# USB.net
KiCad netlist of a schematic drawn in Altium Designer
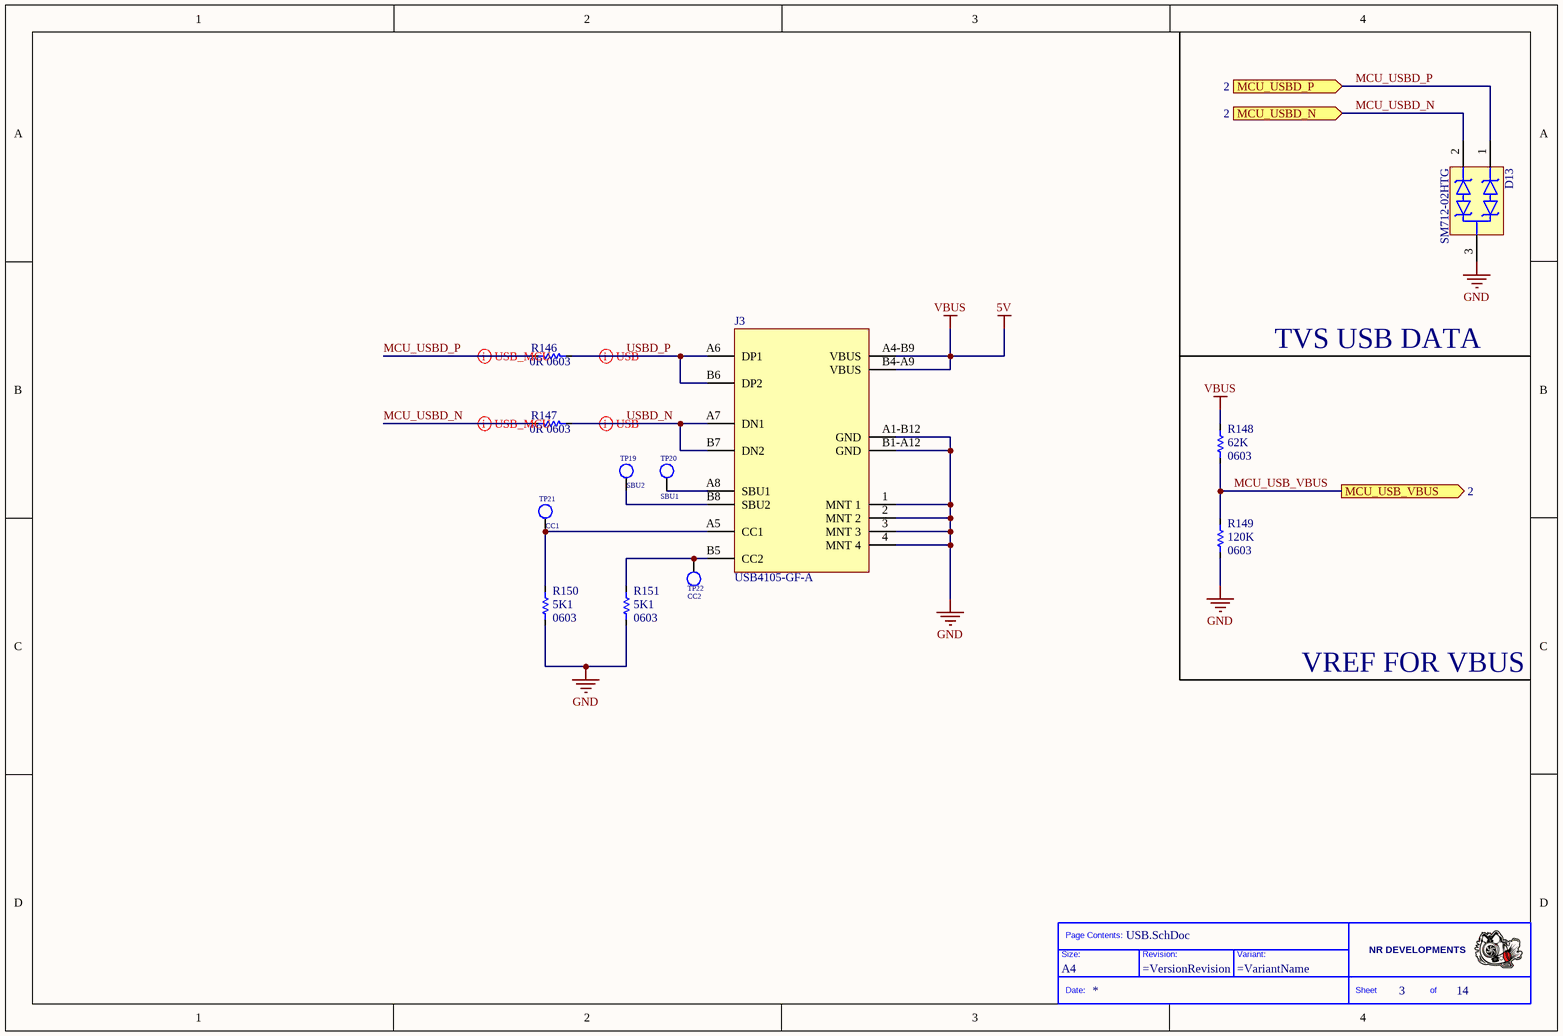
[diagram p0: USB.SchDoc]

(export (version "E")
  (design (tool "Eeschema 10.0.6"))
  (components
    (comp (ref "D13")
      (value "SM712-02HTG")
      (footprint "SOT95P240X120-3N")
      (description "ESD Diode bid -7 to 12v")
      (fields (field (name "MANUFACTURER") "Littelfuse"))
      (libsource (lib "My_LIB") (part "SM712-02HTG"))
    )
    (comp (ref "J3")
      (value "USB4105-GF-A")
      (footprint "GCT-USB4105-GF-A")
      (description "USB Connectors USB Type C,2.0, Rec,SMT, 0.95mmTH Shell Stakes,G/F,RA,Top Mnt,T&R")
      (fields (field (name "MANUFACTURER") "GCT"))
      (libsource (lib "My_LIB") (part "USB4105-GF-A"))
    )
    (comp (ref "R146")
      (value "0R")
      (footprint "RESC1608X06M")
      (description "CRCW06030000Z0EAC")
      (fields
        (field (name "CASE") "0603")
        (field (name "MANUFACTURER") "YAGEO")
        (field (name "PARTNUMBER") "RC0603JR-070RL")
      )
      (libsource (lib "My_LIB") (part "Resistor"))
    )
    (comp (ref "R147")
      (value "0R")
      (footprint "RESC1608X06M")
      (description "CRCW06030000Z0EAC")
      (fields
        (field (name "CASE") "0603")
        (field (name "MANUFACTURER") "YAGEO")
        (field (name "PARTNUMBER") "RC0603JR-070RL")
      )
      (libsource (lib "My_LIB") (part "Resistor"))
    )
    (comp (ref "R148")
      (value "62K")
      (footprint "RESC1608X06M")
      (description "Resistor")
      (fields
        (field (name "MANUFACTURER") "Vishay")
        (field (name "CASE") "0603")
        (field (name "PARTNUMBER") "CRCW06035K10FKEC")
      )
      (libsource (lib "My_LIB") (part "Resistor"))
    )
    (comp (ref "R149")
      (value "120K")
      (footprint "RESC1608X06M")
      (description "Resistor")
      (fields
        (field (name "MANUFACTURER") "Vishay")
        (field (name "CASE") "0603")
        (field (name "PARTNUMBER") "CRCW06035K10FKEC")
      )
      (libsource (lib "My_LIB") (part "Resistor"))
    )
    (comp (ref "R150")
      (value "5K1")
      (footprint "RESC1608X06M")
      (fields
        (field (name "MANUFACTURER") "Vishay")
        (field (name "CASE") "0603")
        (field (name "PARTNUMBER") "CRCW06035K10FKEC")
        (field (name "Comment") "Resistor")
      )
      (libsource (lib "My_LIB") (part "Resistor"))
    )
    (comp (ref "R151")
      (value "5K1")
      (footprint "RESC1608X06M")
      (fields
        (field (name "MANUFACTURER") "Vishay")
        (field (name "CASE") "0603")
        (field (name "PARTNUMBER") "CRCW06035K10FKEC")
        (field (name "Comment") "Resistor")
      )
      (libsource (lib "My_LIB") (part "Resistor"))
    )
    (comp (ref "TP19")
      (value "SBU2")
      (footprint "TP_c200")
      (description "Test Poin")
      (libsource (lib "My_LIB") (part "Test_Point"))
    )
    (comp (ref "TP20")
      (value "SBU1")
      (footprint "TP_c200")
      (description "Test Poin")
      (libsource (lib "My_LIB") (part "Test_Point"))
    )
    (comp (ref "TP21")
      (value "CC1")
      (footprint "TP_c200")
      (description "Test Poin")
      (libsource (lib "My_LIB") (part "Test_Point"))
    )
    (comp (ref "TP22")
      (value "CC2")
      (footprint "TP_c200")
      (description "Test Poin")
      (libsource (lib "My_LIB") (part "Test_Point"))
    )
  )
  (nets
    (net (code "1") (name "/MCU_USBD_N") (class "Default")
      (node (ref "D13") (pin "2") (pinfunction "2_2") (pintype "passive"))
      (node (ref "R147") (pin "1") (pinfunction "1_1") (pintype "passive"))
    )
    (net (code "2") (name "/MCU_USBD_P") (class "Default")
      (node (ref "D13") (pin "1") (pinfunction "1_1") (pintype "passive"))
      (node (ref "R146") (pin "1") (pinfunction "1_1") (pintype "passive"))
    )
    (net (code "3") (name "/MCU_USB_VBUS") (class "Default")
      (node (ref "R148") (pin "1") (pinfunction "1_1") (pintype "passive"))
      (node (ref "R149") (pin "2") (pinfunction "2_2") (pintype "passive"))
    )
    (net (code "4") (name "/USBD_N") (class "Default")
      (node (ref "J3") (pin "A7") (pinfunction "DN1_A7") (pintype "passive"))
      (node (ref "J3") (pin "B7") (pinfunction "DN2_B7") (pintype "passive"))
      (node (ref "R147") (pin "2") (pinfunction "2_2") (pintype "passive"))
    )
    (net (code "5") (name "/USBD_P") (class "Default")
      (node (ref "J3") (pin "A6") (pinfunction "DP1_A6") (pintype "passive"))
      (node (ref "J3") (pin "B6") (pinfunction "DP2_B6") (pintype "passive"))
      (node (ref "R146") (pin "2") (pinfunction "2_2") (pintype "passive"))
    )
    (net (code "6") (name "5V") (class "Default")
      (node (ref "J3") (pin "A4-B9") (pinfunction "VBUS_A4-B9") (pintype "passive"))
      (node (ref "J3") (pin "B4-A9") (pinfunction "VBUS_B4-A9") (pintype "passive"))
      (node (ref "R148") (pin "2") (pinfunction "2_2") (pintype "passive"))
    )
    (net (code "7") (name "GND") (class "Default")
      (node (ref "D13") (pin "3") (pinfunction "3_3") (pintype "passive"))
      (node (ref "J3") (pin "1") (pinfunction "MNT_1_1") (pintype "passive"))
      (node (ref "J3") (pin "2") (pinfunction "MNT_2_2") (pintype "passive"))
      (node (ref "J3") (pin "3") (pinfunction "MNT_3_3") (pintype "passive"))
      (node (ref "J3") (pin "4") (pinfunction "MNT_4_4") (pintype "passive"))
      (node (ref "J3") (pin "A1-B12") (pinfunction "GND_A1-B12") (pintype "passive"))
      (node (ref "J3") (pin "B1-A12") (pinfunction "GND_B1-A12") (pintype "passive"))
      (node (ref "R149") (pin "1") (pinfunction "1_1") (pintype "passive"))
      (node (ref "R150") (pin "1") (pinfunction "1_1") (pintype "passive"))
      (node (ref "R151") (pin "1") (pinfunction "1_1") (pintype "passive"))
    )
    (net (code "8") (name "Net-(J3-CC1)") (class "Default")
      (node (ref "J3") (pin "A5") (pinfunction "CC1_A5") (pintype "passive"))
      (node (ref "R150") (pin "2") (pinfunction "2_2") (pintype "passive"))
      (node (ref "TP21") (pin "1") (pinfunction "1_1") (pintype "passive"))
    )
    (net (code "9") (name "Net-(J3-CC2)") (class "Default")
      (node (ref "J3") (pin "B5") (pinfunction "CC2_B5") (pintype "passive"))
      (node (ref "R151") (pin "2") (pinfunction "2_2") (pintype "passive"))
      (node (ref "TP22") (pin "1") (pinfunction "1_1") (pintype "passive"))
    )
    (net (code "10") (name "Net-(J3-SBU1)") (class "Default")
      (node (ref "J3") (pin "A8") (pinfunction "SBU1_A8") (pintype "passive"))
      (node (ref "TP20") (pin "1") (pinfunction "1_1") (pintype "passive"))
    )
    (net (code "11") (name "Net-(J3-SBU2)") (class "Default")
      (node (ref "J3") (pin "B8") (pinfunction "SBU2_B8") (pintype "passive"))
      (node (ref "TP19") (pin "1") (pinfunction "1_1") (pintype "passive"))
    )
  )
)
